# sesam_v2.net
KiCad netlist of a schematic drawn in EAGLE
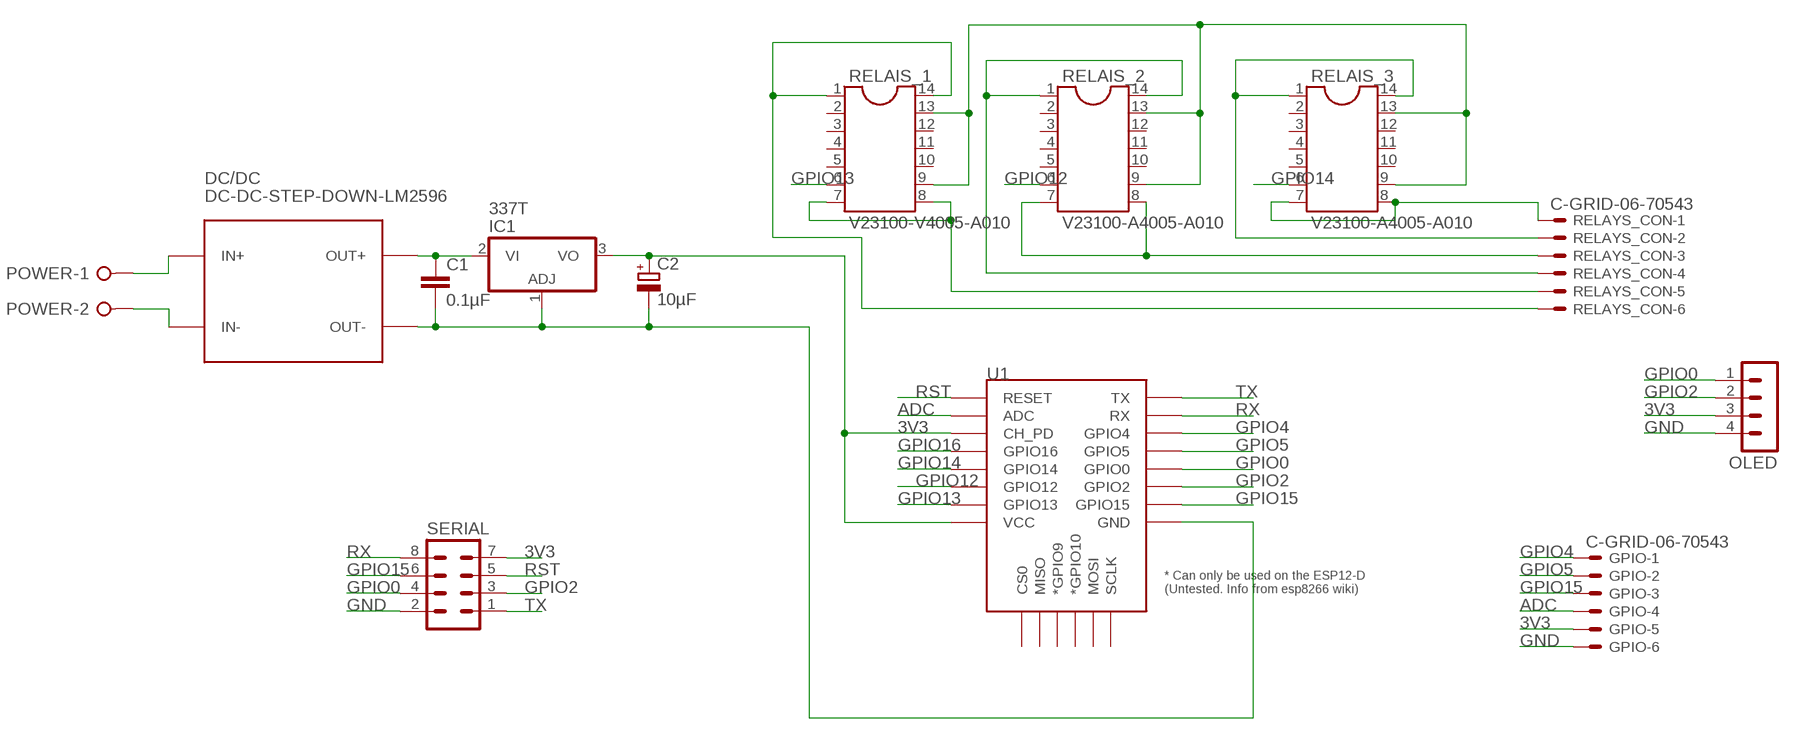
[diagram p0: schematic, sheet 1]

(export (version "E")
  (design (tool "Eeschema 10.0.6"))
  (components
    (comp (ref "C1")
      (value "0.1µF")
      (footprint "eagle-import:C0805")
      (libsource (lib "eagle-import") (part "C-EUC0805"))
    )
    (comp (ref "C2")
      (value "10µF")
      (footprint "eagle-import:E2-5")
      (libsource (lib "eagle-import") (part "CPOL-EUE2-5"))
    )
    (comp (ref "DC/DC")
      (value "DC-DC-STEP-DOWN-LM2596")
      (footprint "eagle-import:DC-DC-STEP-DOWN-LM2596")
      (libsource (lib "eagle-import") (part "DC-DC-STEP-DOWN-LM2596"))
    )
    (comp (ref "GPIO")
      (value "C-GRID-06-70543")
      (footprint "eagle-import:70543-06")
      (libsource (lib "eagle-import") (part "C-GRID-06-70543"))
    )
    (comp (ref "IC1")
      (value "337T")
      (footprint "eagle-import:TO220H")
      (libsource (lib "eagle-import") (part "337T"))
    )
    (comp (ref "OLED")
      (value "MA04-1")
      (footprint "eagle-import:MA04-1")
      (libsource (lib "eagle-import") (part "MA04-1"))
    )
    (comp (ref "POWER")
      (value "W237-02P")
      (footprint "eagle-import:W237-132")
      (libsource (lib "eagle-import") (part "W237-02P"))
    )
    (comp (ref "RELAIS_1")
      (value "V23100-V4005-A010")
      (footprint "eagle-import:SOCKET-14")
      (libsource (lib "eagle-import") (part "DIL14S"))
    )
    (comp (ref "RELAIS_2")
      (value "V23100-A4005-A010")
      (footprint "eagle-import:SOCKET-14")
      (libsource (lib "eagle-import") (part "DIL14S"))
    )
    (comp (ref "RELAIS_3")
      (value "V23100-A4005-A010")
      (footprint "eagle-import:SOCKET-14")
      (libsource (lib "eagle-import") (part "DIL14S"))
    )
    (comp (ref "RELAYS_CON")
      (value "C-GRID-06-70543")
      (footprint "eagle-import:70543-06")
      (libsource (lib "eagle-import") (part "C-GRID-06-70543"))
    )
    (comp (ref "SERIAL")
      (value "MA04-2")
      (footprint "eagle-import:MA04-2")
      (libsource (lib "eagle-import") (part "MA04-2"))
    )
    (comp (ref "U1")
      (value "ESP12ESMD")
      (footprint "eagle-import:ESP12E-SMD")
      (libsource (lib "eagle-import") (part "ESP12ESMD"))
    )
  )
  (nets
    (net (code "1") (name "/3V3") (class "Default")
      (node (ref "C2") (pin "+") (pinfunction "+_+") (pintype "passive"))
      (node (ref "GPIO") (pin "5") (pinfunction "S_5") (pintype "passive"))
      (node (ref "IC1") (pin "3") (pinfunction "VO_3") (pintype "passive"))
      (node (ref "OLED") (pin "3") (pinfunction "3_3") (pintype "passive"))
      (node (ref "SERIAL") (pin "7") (pinfunction "7_7") (pintype "passive"))
      (node (ref "U1") (pin "CH_PD") (pinfunction "CH_PD_CH_PD") (pintype "bidirectional"))
      (node (ref "U1") (pin "VCC") (pinfunction "VCC_VCC") (pintype "bidirectional"))
    )
    (net (code "2") (name "/ADC") (class "Default")
      (node (ref "GPIO") (pin "4") (pinfunction "S_4") (pintype "passive"))
      (node (ref "U1") (pin "ADC") (pinfunction "ADC_ADC") (pintype "bidirectional"))
    )
    (net (code "3") (name "/GND") (class "Default")
      (node (ref "C1") (pin "2") (pinfunction "2_2") (pintype "passive"))
      (node (ref "C2") (pin "-") (pinfunction "-_-") (pintype "passive"))
      (node (ref "DC/DC") (pin "IN-") (pinfunction "IN-_IN-") (pintype "bidirectional"))
      (node (ref "DC/DC") (pin "OUT-") (pinfunction "OUT-_OUT-") (pintype "bidirectional"))
      (node (ref "GPIO") (pin "6") (pinfunction "S_6") (pintype "passive"))
      (node (ref "IC1") (pin "1") (pinfunction "ADJ_1") (pintype "input"))
      (node (ref "OLED") (pin "4") (pinfunction "4_4") (pintype "passive"))
      (node (ref "POWER") (pin "2") (pinfunction "KL_2") (pintype "passive"))
      (node (ref "RELAIS_1") (pin "13") (pinfunction "13_13") (pintype "passive"))
      (node (ref "RELAIS_1") (pin "9") (pinfunction "9_9") (pintype "passive"))
      (node (ref "RELAIS_2") (pin "13") (pinfunction "13_13") (pintype "passive"))
      (node (ref "RELAIS_2") (pin "9") (pinfunction "9_9") (pintype "passive"))
      (node (ref "RELAIS_3") (pin "13") (pinfunction "13_13") (pintype "passive"))
      (node (ref "RELAIS_3") (pin "9") (pinfunction "9_9") (pintype "passive"))
      (node (ref "SERIAL") (pin "2") (pinfunction "2_2") (pintype "passive"))
      (node (ref "U1") (pin "GND") (pinfunction "GND_GND") (pintype "bidirectional"))
    )
    (net (code "4") (name "/GPIO0") (class "Default")
      (node (ref "OLED") (pin "1") (pinfunction "1_1") (pintype "passive"))
      (node (ref "SERIAL") (pin "4") (pinfunction "4_4") (pintype "passive"))
      (node (ref "U1") (pin "GPIO0") (pinfunction "GPIO0_GPIO0") (pintype "bidirectional"))
    )
    (net (code "5") (name "/GPIO2") (class "Default")
      (node (ref "OLED") (pin "2") (pinfunction "2_2") (pintype "passive"))
      (node (ref "SERIAL") (pin "3") (pinfunction "3_3") (pintype "passive"))
      (node (ref "U1") (pin "GPIO2") (pinfunction "GPIO2_GPIO2") (pintype "bidirectional"))
    )
    (net (code "6") (name "/GPIO4") (class "Default")
      (node (ref "GPIO") (pin "1") (pinfunction "S_1") (pintype "passive"))
      (node (ref "U1") (pin "GPIO4") (pinfunction "GPIO4_GPIO4") (pintype "bidirectional"))
    )
    (net (code "7") (name "/GPIO5") (class "Default")
      (node (ref "GPIO") (pin "2") (pinfunction "S_2") (pintype "passive"))
      (node (ref "U1") (pin "GPIO5") (pinfunction "GPIO5_GPIO5") (pintype "bidirectional"))
    )
    (net (code "8") (name "/GPIO12") (class "Default")
      (node (ref "RELAIS_2") (pin "6") (pinfunction "6_6") (pintype "passive"))
      (node (ref "U1") (pin "GPIO12") (pinfunction "GPIO12_GPIO12") (pintype "bidirectional"))
    )
    (net (code "9") (name "/GPIO13") (class "Default")
      (node (ref "RELAIS_1") (pin "6") (pinfunction "6_6") (pintype "passive"))
      (node (ref "U1") (pin "GPIO13") (pinfunction "GPIO13_GPIO13") (pintype "bidirectional"))
    )
    (net (code "10") (name "/GPIO14") (class "Default")
      (node (ref "RELAIS_3") (pin "6") (pinfunction "6_6") (pintype "passive"))
      (node (ref "U1") (pin "GPIO14") (pinfunction "GPIO14_GPIO14") (pintype "bidirectional"))
    )
    (net (code "11") (name "/GPIO15") (class "Default")
      (node (ref "GPIO") (pin "3") (pinfunction "S_3") (pintype "passive"))
      (node (ref "SERIAL") (pin "6") (pinfunction "6_6") (pintype "passive"))
      (node (ref "U1") (pin "GPIO15") (pinfunction "GPIO15_GPIO15") (pintype "bidirectional"))
    )
    (net (code "12") (name "/GPIO16") (class "Default")
      (node (ref "U1") (pin "GPIO16") (pinfunction "GPIO16_GPIO16") (pintype "bidirectional"))
    )
    (net (code "13") (name "/RST") (class "Default")
      (node (ref "SERIAL") (pin "5") (pinfunction "5_5") (pintype "passive"))
      (node (ref "U1") (pin "RESET") (pinfunction "RESET_RESET") (pintype "bidirectional"))
    )
    (net (code "14") (name "/RX") (class "Default")
      (node (ref "SERIAL") (pin "8") (pinfunction "8_8") (pintype "passive"))
      (node (ref "U1") (pin "RXD0") (pinfunction "RX_RXD0") (pintype "bidirectional"))
    )
    (net (code "15") (name "/TX") (class "Default")
      (node (ref "SERIAL") (pin "1") (pinfunction "1_1") (pintype "passive"))
      (node (ref "U1") (pin "TXD0") (pinfunction "TX_TXD0") (pintype "bidirectional"))
    )
    (net (code "16") (name "Net-(IC1-VI)") (class "Default")
      (node (ref "C1") (pin "1") (pinfunction "1_1") (pintype "passive"))
      (node (ref "DC/DC") (pin "OUT+") (pinfunction "OUT+_OUT+") (pintype "bidirectional"))
      (node (ref "IC1") (pin "2") (pinfunction "VI_2") (pintype "input"))
    )
    (net (code "17") (name "Net-(POWERA-KL)") (class "Default")
      (node (ref "DC/DC") (pin "IN+") (pinfunction "IN+_IN+") (pintype "bidirectional"))
      (node (ref "POWER") (pin "1") (pinfunction "KL_1") (pintype "passive"))
    )
    (net (code "18") (name "Net-(RELAYS_CONA-S)") (class "Default")
      (node (ref "RELAIS_3") (pin "7") (pinfunction "7_7") (pintype "passive"))
      (node (ref "RELAIS_3") (pin "8") (pinfunction "8_8") (pintype "passive"))
      (node (ref "RELAYS_CON") (pin "1") (pinfunction "S_1") (pintype "passive"))
    )
    (net (code "19") (name "Net-(RELAYS_CONB-S)") (class "Default")
      (node (ref "RELAIS_3") (pin "1") (pinfunction "1_1") (pintype "passive"))
      (node (ref "RELAIS_3") (pin "14") (pinfunction "14_14") (pintype "passive"))
      (node (ref "RELAYS_CON") (pin "2") (pinfunction "S_2") (pintype "passive"))
    )
    (net (code "20") (name "Net-(RELAYS_CONC-S)") (class "Default")
      (node (ref "RELAIS_2") (pin "7") (pinfunction "7_7") (pintype "passive"))
      (node (ref "RELAIS_2") (pin "8") (pinfunction "8_8") (pintype "passive"))
      (node (ref "RELAYS_CON") (pin "3") (pinfunction "S_3") (pintype "passive"))
    )
    (net (code "21") (name "Net-(RELAYS_COND-S)") (class "Default")
      (node (ref "RELAIS_2") (pin "1") (pinfunction "1_1") (pintype "passive"))
      (node (ref "RELAIS_2") (pin "14") (pinfunction "14_14") (pintype "passive"))
      (node (ref "RELAYS_CON") (pin "4") (pinfunction "S_4") (pintype "passive"))
    )
    (net (code "22") (name "Net-(RELAYS_CONE-S)") (class "Default")
      (node (ref "RELAIS_1") (pin "7") (pinfunction "7_7") (pintype "passive"))
      (node (ref "RELAIS_1") (pin "8") (pinfunction "8_8") (pintype "passive"))
      (node (ref "RELAYS_CON") (pin "5") (pinfunction "S_5") (pintype "passive"))
    )
    (net (code "23") (name "Net-(RELAYS_CONF-S)") (class "Default")
      (node (ref "RELAIS_1") (pin "1") (pinfunction "1_1") (pintype "passive"))
      (node (ref "RELAIS_1") (pin "14") (pinfunction "14_14") (pintype "passive"))
      (node (ref "RELAYS_CON") (pin "6") (pinfunction "S_6") (pintype "passive"))
    )
    (net (code "24") (name "unconnected-(RELAIS_1-Pad2)") (class "Default")
      (node (ref "RELAIS_1") (pin "2") (pinfunction "2_2") (pintype "passive"))
    )
    (net (code "25") (name "unconnected-(RELAIS_1-Pad3)") (class "Default")
      (node (ref "RELAIS_1") (pin "3") (pinfunction "3_3") (pintype "passive"))
    )
    (net (code "26") (name "unconnected-(RELAIS_1-Pad4)") (class "Default")
      (node (ref "RELAIS_1") (pin "4") (pinfunction "4_4") (pintype "passive"))
    )
    (net (code "27") (name "unconnected-(RELAIS_1-Pad5)") (class "Default")
      (node (ref "RELAIS_1") (pin "5") (pinfunction "5_5") (pintype "passive"))
    )
    (net (code "28") (name "unconnected-(RELAIS_1-Pad10)") (class "Default")
      (node (ref "RELAIS_1") (pin "10") (pinfunction "10_10") (pintype "passive"))
    )
    (net (code "29") (name "unconnected-(RELAIS_1-Pad11)") (class "Default")
      (node (ref "RELAIS_1") (pin "11") (pinfunction "11_11") (pintype "passive"))
    )
    (net (code "30") (name "unconnected-(RELAIS_1-Pad12)") (class "Default")
      (node (ref "RELAIS_1") (pin "12") (pinfunction "12_12") (pintype "passive"))
    )
    (net (code "31") (name "unconnected-(RELAIS_2-Pad2)") (class "Default")
      (node (ref "RELAIS_2") (pin "2") (pinfunction "2_2") (pintype "passive"))
    )
    (net (code "32") (name "unconnected-(RELAIS_2-Pad3)") (class "Default")
      (node (ref "RELAIS_2") (pin "3") (pinfunction "3_3") (pintype "passive"))
    )
    (net (code "33") (name "unconnected-(RELAIS_2-Pad4)") (class "Default")
      (node (ref "RELAIS_2") (pin "4") (pinfunction "4_4") (pintype "passive"))
    )
    (net (code "34") (name "unconnected-(RELAIS_2-Pad5)") (class "Default")
      (node (ref "RELAIS_2") (pin "5") (pinfunction "5_5") (pintype "passive"))
    )
    (net (code "35") (name "unconnected-(RELAIS_2-Pad10)") (class "Default")
      (node (ref "RELAIS_2") (pin "10") (pinfunction "10_10") (pintype "passive"))
    )
    (net (code "36") (name "unconnected-(RELAIS_2-Pad11)") (class "Default")
      (node (ref "RELAIS_2") (pin "11") (pinfunction "11_11") (pintype "passive"))
    )
    (net (code "37") (name "unconnected-(RELAIS_2-Pad12)") (class "Default")
      (node (ref "RELAIS_2") (pin "12") (pinfunction "12_12") (pintype "passive"))
    )
    (net (code "38") (name "unconnected-(RELAIS_3-Pad2)") (class "Default")
      (node (ref "RELAIS_3") (pin "2") (pinfunction "2_2") (pintype "passive"))
    )
    (net (code "39") (name "unconnected-(RELAIS_3-Pad3)") (class "Default")
      (node (ref "RELAIS_3") (pin "3") (pinfunction "3_3") (pintype "passive"))
    )
    (net (code "40") (name "unconnected-(RELAIS_3-Pad4)") (class "Default")
      (node (ref "RELAIS_3") (pin "4") (pinfunction "4_4") (pintype "passive"))
    )
    (net (code "41") (name "unconnected-(RELAIS_3-Pad5)") (class "Default")
      (node (ref "RELAIS_3") (pin "5") (pinfunction "5_5") (pintype "passive"))
    )
    (net (code "42") (name "unconnected-(RELAIS_3-Pad10)") (class "Default")
      (node (ref "RELAIS_3") (pin "10") (pinfunction "10_10") (pintype "passive"))
    )
    (net (code "43") (name "unconnected-(RELAIS_3-Pad11)") (class "Default")
      (node (ref "RELAIS_3") (pin "11") (pinfunction "11_11") (pintype "passive"))
    )
    (net (code "44") (name "unconnected-(RELAIS_3-Pad12)") (class "Default")
      (node (ref "RELAIS_3") (pin "12") (pinfunction "12_12") (pintype "passive"))
    )
    (net (code "45") (name "unconnected-(U1-*GPIO9-PadGPIO9)") (class "Default")
      (node (ref "U1") (pin "GPIO9") (pinfunction "*GPIO9_GPIO9") (pintype "bidirectional"))
    )
    (net (code "46") (name "unconnected-(U1-*GPIO10-PadGPIO10)") (class "Default")
      (node (ref "U1") (pin "GPIO10") (pinfunction "*GPIO10_GPIO10") (pintype "bidirectional"))
    )
    (net (code "47") (name "unconnected-(U1-PadCS0)") (class "Default")
      (node (ref "U1") (pin "CS0") (pinfunction "CS0_CS0") (pintype "bidirectional"))
    )
    (net (code "48") (name "unconnected-(U1-PadMISO)") (class "Default")
      (node (ref "U1") (pin "MISO") (pinfunction "MISO_MISO") (pintype "bidirectional"))
    )
    (net (code "49") (name "unconnected-(U1-PadMOSI)") (class "Default")
      (node (ref "U1") (pin "MOSI") (pinfunction "MOSI_MOSI") (pintype "bidirectional"))
    )
    (net (code "50") (name "unconnected-(U1-PadSCLK)") (class "Default")
      (node (ref "U1") (pin "SCLK") (pinfunction "SCLK_SCLK") (pintype "bidirectional"))
    )
  )
)
